# omca_to_mega_1.net
KiCad netlist of a schematic drawn in EAGLE
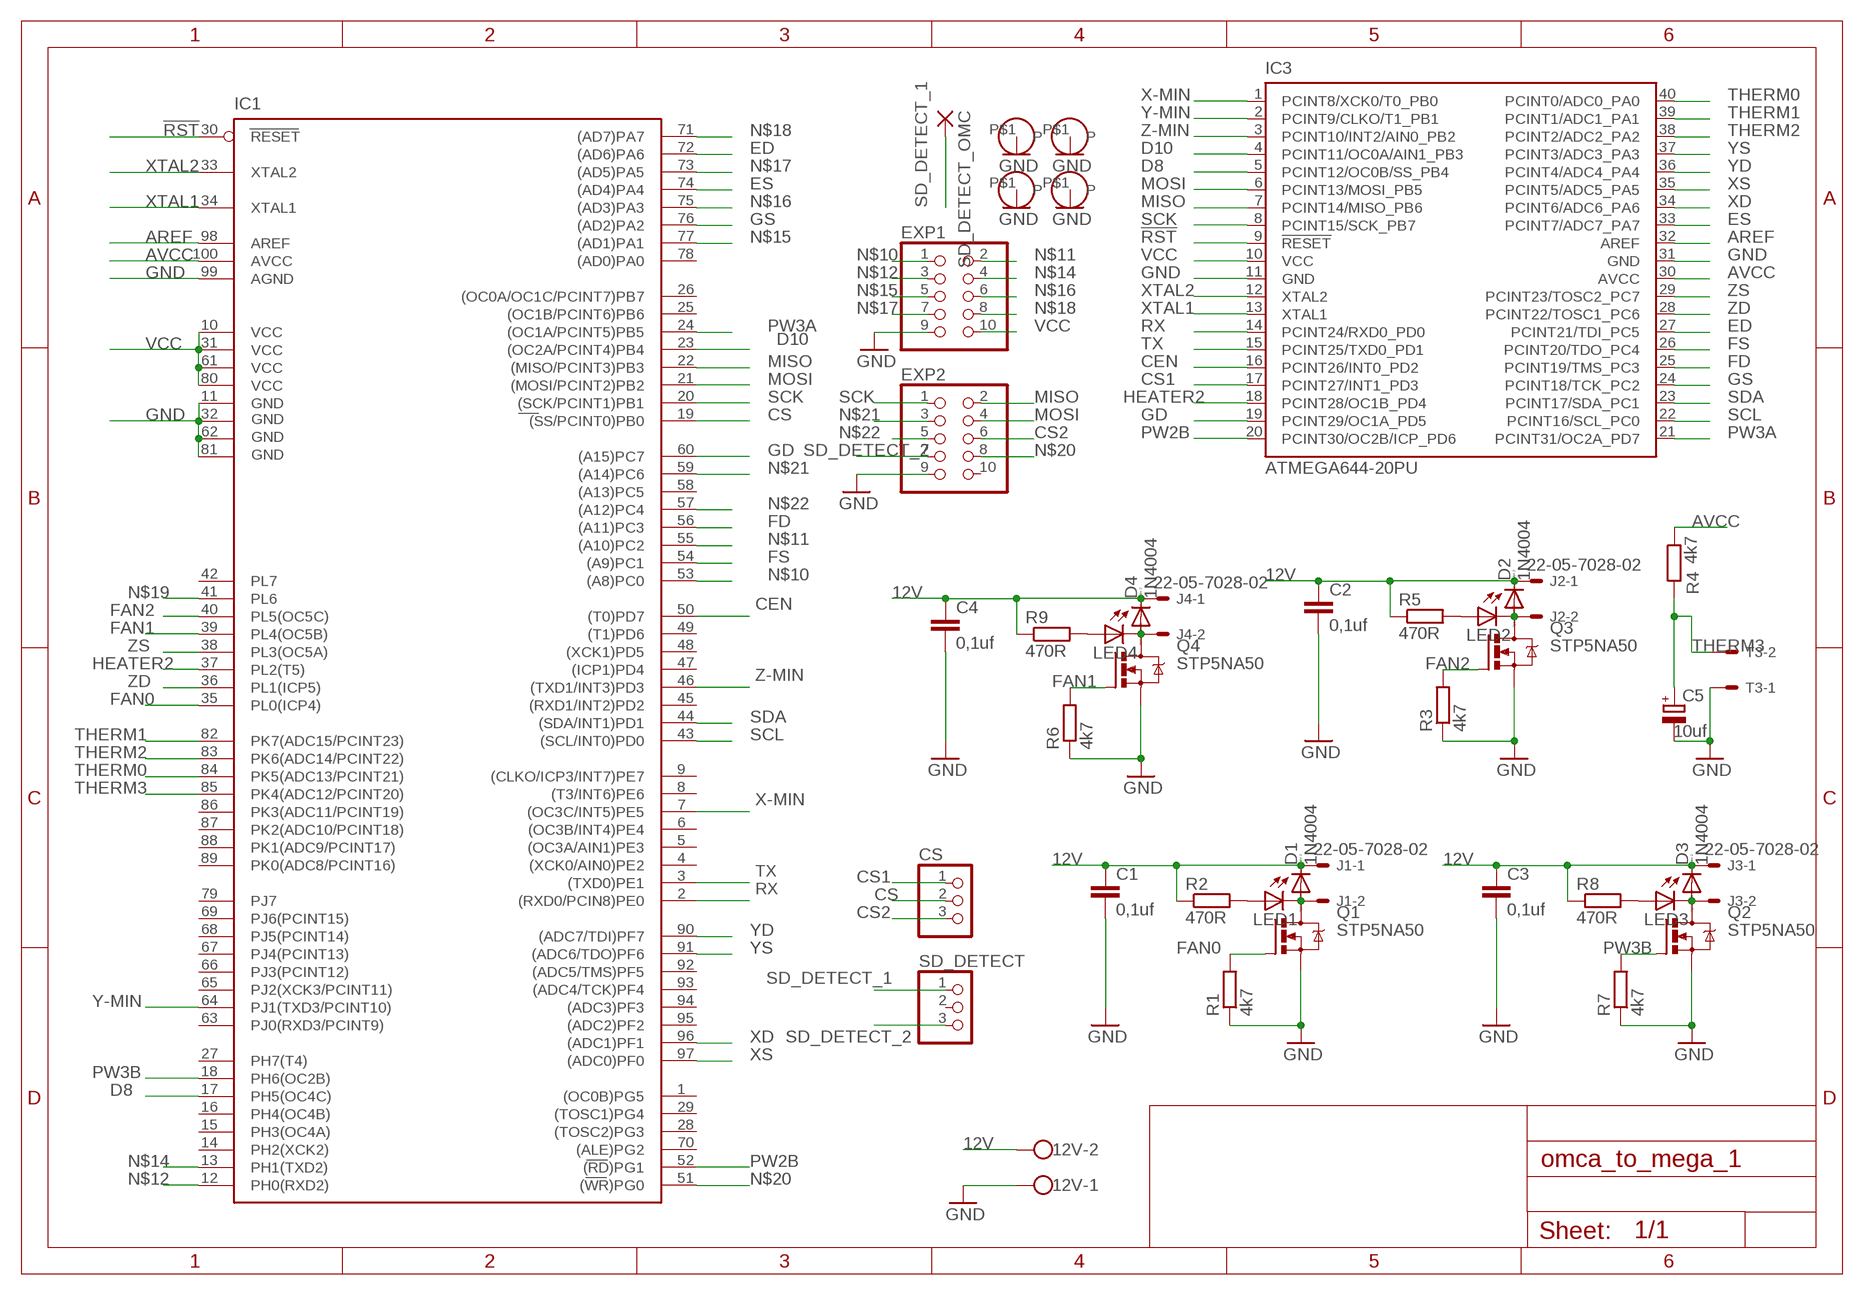
[diagram p0: schematic, sheet 1]

(export (version "E")
  (design (tool "Eeschema 10.0.6"))
  (components
    (comp (ref "12V")
      (value "W237-102")
      (footprint "eagle-import:W237-102")
      (fields (field (name "MPN") "237-102"))
      (libsource (lib "eagle-import") (part "W237-102"))
    )
    (comp (ref "C1")
      (value "0,1uf")
      (footprint "eagle-import:C025-024X044")
      (fields (field (name "MF") "VISHAY") (field (name "MPN") "K104K15X7RF53L2"))
      (libsource (lib "eagle-import") (part "C-EU025-024X044"))
    )
    (comp (ref "C2")
      (value "0,1uf")
      (footprint "eagle-import:C025-024X044")
      (fields (field (name "MF") "VISHAY") (field (name "MPN") "K104K15X7RF53L2"))
      (libsource (lib "eagle-import") (part "C-EU025-024X044"))
    )
    (comp (ref "C3")
      (value "0,1uf")
      (footprint "eagle-import:C025-024X044")
      (fields (field (name "MF") "VISHAY") (field (name "MPN") "K104K15X7RF53L2"))
      (libsource (lib "eagle-import") (part "C-EU025-024X044"))
    )
    (comp (ref "C4")
      (value "0,1uf")
      (footprint "eagle-import:C025-024X044")
      (fields (field (name "MF") "VISHAY") (field (name "MPN") "K104K15X7RF53L2"))
      (libsource (lib "eagle-import") (part "C-EU025-024X044"))
    )
    (comp (ref "C5")
      (value "10uf")
      (footprint "eagle-import:TT2D4")
      (fields (field (name "MF") "RUBYCON") (field (name "MPN") "100YXF10MEFC6.3X11"))
      (libsource (lib "eagle-import") (part "CPOL-EUTT2D4"))
    )
    (comp (ref "CS")
      (value "PINHD-1X3")
      (footprint "eagle-import:1X03")
      (libsource (lib "eagle-import") (part "PINHD-1X3"))
    )
    (comp (ref "D1")
      (value "1N4004")
      (footprint "eagle-import:D-7.5")
      (fields (field (name "MF") "ON SEMICONDUCTOR") (field (name "MPN") "1N4004RL"))
      (libsource (lib "eagle-import") (part "DIODE-D-7.5"))
    )
    (comp (ref "D2")
      (value "1N4004")
      (footprint "eagle-import:D-7.5")
      (fields (field (name "MF") "ON SEMICONDUCTOR") (field (name "MPN") "1N4004RL"))
      (libsource (lib "eagle-import") (part "DIODE-D-7.5"))
    )
    (comp (ref "D3")
      (value "1N4004")
      (footprint "eagle-import:D-7.5")
      (fields (field (name "MF") "ON SEMICONDUCTOR") (field (name "MPN") "1N4004RL"))
      (libsource (lib "eagle-import") (part "DIODE-D-7.5"))
    )
    (comp (ref "D4")
      (value "1N4004")
      (footprint "eagle-import:D-7.5")
      (fields (field (name "MF") "ON SEMICONDUCTOR") (field (name "MPN") "1N4004RL"))
      (libsource (lib "eagle-import") (part "DIODE-D-7.5"))
    )
    (comp (ref "EXP1")
      (value "PINHD-2X5")
      (footprint "eagle-import:2X05")
      (libsource (lib "eagle-import") (part "PINHD-2X5"))
    )
    (comp (ref "EXP2")
      (value "PINHD-2X5")
      (footprint "eagle-import:2X05")
      (libsource (lib "eagle-import") (part "PINHD-2X5"))
    )
    (comp (ref "IC1")
      (value "ATMEGA2560-16AU")
      (footprint "eagle-import:TQFP100")
      (libsource (lib "eagle-import") (part "ATMEGA2560AU2560-16"))
    )
    (comp (ref "IC3")
      (value "ATMEGA644-20PU")
      (footprint "eagle-import:DIL40")
      (fields
        (field (name "MF") "ATMEL")
        (field (name "MPN") "ATMEGA644-20PU")
        (field (name "OC_FARNELL") "1288340")
      )
      (libsource (lib "eagle-import") (part "ATMEGA644-PU20"))
    )
    (comp (ref "J1")
      (value "22-05-7028-02")
      (footprint "eagle-import:7395-02")
      (fields
        (field (name "MF") "MOLEX")
        (field (name "MPN") "22-05-7028")
        (field (name "OC_FARNELL") "9731601")
      )
      (libsource (lib "eagle-import") (part "22-?-0205-7028"))
    )
    (comp (ref "J2")
      (value "22-05-7028-02")
      (footprint "eagle-import:7395-02")
      (fields
        (field (name "MF") "MOLEX")
        (field (name "MPN") "22-05-7028")
        (field (name "OC_FARNELL") "9731601")
      )
      (libsource (lib "eagle-import") (part "22-?-0205-7028"))
    )
    (comp (ref "J3")
      (value "22-05-7028-02")
      (footprint "eagle-import:7395-02")
      (fields
        (field (name "MF") "MOLEX")
        (field (name "MPN") "22-05-7028")
        (field (name "OC_FARNELL") "9731601")
      )
      (libsource (lib "eagle-import") (part "22-?-0205-7028"))
    )
    (comp (ref "J4")
      (value "22-05-7028-02")
      (footprint "eagle-import:7395-02")
      (fields
        (field (name "MF") "MOLEX")
        (field (name "MPN") "22-05-7028")
        (field (name "OC_FARNELL") "9731601")
      )
      (libsource (lib "eagle-import") (part "22-?-0205-7028"))
    )
    (comp (ref "LED1")
      (value "LED3MM")
      (footprint "eagle-import:LED3MM")
      (fields (field (name "MF") "KINGBRIGHT") (field (name "MPN") "L-93WEYW"))
      (libsource (lib "eagle-import") (part "LED3MM"))
    )
    (comp (ref "LED2")
      (value "LED3MM")
      (footprint "eagle-import:LED3MM")
      (fields (field (name "MF") "KINGBRIGHT") (field (name "MPN") "L-93WEYW"))
      (libsource (lib "eagle-import") (part "LED3MM"))
    )
    (comp (ref "LED3")
      (value "LED3MM")
      (footprint "eagle-import:LED3MM")
      (fields (field (name "MF") "KINGBRIGHT") (field (name "MPN") "L-93WEYW"))
      (libsource (lib "eagle-import") (part "LED3MM"))
    )
    (comp (ref "LED4")
      (value "LED3MM")
      (footprint "eagle-import:LED3MM")
      (fields (field (name "MF") "KINGBRIGHT") (field (name "MPN") "L-93WEYW"))
      (libsource (lib "eagle-import") (part "LED3MM"))
    )
    (comp (ref "Q1")
      (value "STP5NA50")
      (footprint "eagle-import:TO220BV")
      (fields (field (name "MF") "STMICROELECTRONICS") (field (name "MPN") "STP55NF06L."))
      (libsource (lib "eagle-import") (part "STP5NA50"))
    )
    (comp (ref "Q2")
      (value "STP5NA50")
      (footprint "eagle-import:TO220BV")
      (fields (field (name "MF") "STMICROELECTRONICS") (field (name "MPN") "STP55NF06L."))
      (libsource (lib "eagle-import") (part "STP5NA50"))
    )
    (comp (ref "Q3")
      (value "STP5NA50")
      (footprint "eagle-import:TO220BV")
      (fields (field (name "MF") "STMICROELECTRONICS") (field (name "MPN") "STP55NF06L."))
      (libsource (lib "eagle-import") (part "STP5NA50"))
    )
    (comp (ref "Q4")
      (value "STP5NA50")
      (footprint "eagle-import:TO220BV")
      (fields (field (name "MF") "STMICROELECTRONICS") (field (name "MPN") "STP55NF06L."))
      (libsource (lib "eagle-import") (part "STP5NA50"))
    )
    (comp (ref "R1")
      (value "4k7")
      (footprint "eagle-import:0204_7")
      (fields (field (name "MF") "WELWYN") (field (name "MPN") "MFR4 10K 1%"))
      (libsource (lib "eagle-import") (part "resistor_R-EU_0204/7"))
    )
    (comp (ref "R2")
      (value "470R")
      (footprint "eagle-import:0204_7")
      (fields (field (name "MF") "WELWYN") (field (name "MPN") "MFR4 470R 1%"))
      (libsource (lib "eagle-import") (part "resistor_R-EU_0204/7"))
    )
    (comp (ref "R3")
      (value "4k7")
      (footprint "eagle-import:0204_7")
      (fields (field (name "MF") "WELWYN") (field (name "MPN") "MFR4 10K 1%"))
      (libsource (lib "eagle-import") (part "resistor_R-EU_0204/7"))
    )
    (comp (ref "R4")
      (value "4k7")
      (footprint "eagle-import:0204_7")
      (fields (field (name "MF") "WELWYN") (field (name "MPN") "MFR4 4K7 1%"))
      (libsource (lib "eagle-import") (part "R-EU_0204/7"))
    )
    (comp (ref "R5")
      (value "470R")
      (footprint "eagle-import:0204_7")
      (fields (field (name "MF") "WELWYN") (field (name "MPN") "MFR4 470R 1%"))
      (libsource (lib "eagle-import") (part "resistor_R-EU_0204/7"))
    )
    (comp (ref "R6")
      (value "4k7")
      (footprint "eagle-import:0204_7")
      (fields (field (name "MF") "WELWYN") (field (name "MPN") "MFR4 10K 1%"))
      (libsource (lib "eagle-import") (part "resistor_R-EU_0204/7"))
    )
    (comp (ref "R7")
      (value "4k7")
      (footprint "eagle-import:0204_7")
      (fields (field (name "MF") "WELWYN") (field (name "MPN") "MFR4 10K 1%"))
      (libsource (lib "eagle-import") (part "resistor_R-EU_0204/7"))
    )
    (comp (ref "R8")
      (value "470R")
      (footprint "eagle-import:0204_7")
      (fields (field (name "MF") "WELWYN") (field (name "MPN") "MFR4 470R 1%"))
      (libsource (lib "eagle-import") (part "resistor_R-EU_0204/7"))
    )
    (comp (ref "R9")
      (value "470R")
      (footprint "eagle-import:0204_7")
      (fields (field (name "MF") "WELWYN") (field (name "MPN") "MFR4 470R 1%"))
      (libsource (lib "eagle-import") (part "resistor_R-EU_0204/7"))
    )
    (comp (ref "SD_DETECT")
      (value "PINHD-1X3")
      (footprint "eagle-import:1X03")
      (libsource (lib "eagle-import") (part "PINHD-1X3"))
    )
    (comp (ref "SD_DETECT_OMC")
      (value "1,6/0,8")
      (footprint "eagle-import:1,6_0,8")
      (libsource (lib "eagle-import") (part "1,6/0,8"))
    )
    (comp (ref "T3")
      (value "22-05-7028-02")
      (footprint "eagle-import:7395-02")
      (fields
        (field (name "MF") "MOLEX")
        (field (name "MPN") "22-05-7028")
        (field (name "OC_FARNELL") "9731601")
      )
      (libsource (lib "eagle-import") (part "22-?-0205-7028"))
    )
    (comp (ref "U$2")
      (value "HOLE")
      (footprint "eagle-import:HOLE")
      (libsource (lib "eagle-import") (part "HOLE"))
    )
    (comp (ref "U$3")
      (value "HOLE")
      (footprint "eagle-import:HOLE")
      (libsource (lib "eagle-import") (part "HOLE"))
    )
    (comp (ref "U$4")
      (value "HOLE")
      (footprint "eagle-import:HOLE")
      (libsource (lib "eagle-import") (part "HOLE"))
    )
    (comp (ref "U$5")
      (value "HOLE")
      (footprint "eagle-import:HOLE")
      (libsource (lib "eagle-import") (part "HOLE"))
    )
  )
  (nets
    (net (code "1") (name "/12V") (class "Default")
      (node (ref "12V") (pin "2") (pinfunction "KL_2") (pintype "passive"))
      (node (ref "C1") (pin "1") (pinfunction "1_1") (pintype "passive"))
      (node (ref "C2") (pin "1") (pinfunction "1_1") (pintype "passive"))
      (node (ref "C3") (pin "1") (pinfunction "1_1") (pintype "passive"))
      (node (ref "C4") (pin "1") (pinfunction "1_1") (pintype "passive"))
      (node (ref "D1") (pin "C") (pinfunction "C_C") (pintype "passive"))
      (node (ref "D2") (pin "C") (pinfunction "C_C") (pintype "passive"))
      (node (ref "D3") (pin "C") (pinfunction "C_C") (pintype "passive"))
      (node (ref "D4") (pin "C") (pinfunction "C_C") (pintype "passive"))
      (node (ref "J1") (pin "1") (pinfunction "S_1") (pintype "passive"))
      (node (ref "J2") (pin "1") (pinfunction "S_1") (pintype "passive"))
      (node (ref "J3") (pin "1") (pinfunction "S_1") (pintype "passive"))
      (node (ref "J4") (pin "1") (pinfunction "S_1") (pintype "passive"))
      (node (ref "R2") (pin "1") (pinfunction "1_1") (pintype "passive"))
      (node (ref "R5") (pin "1") (pinfunction "1_1") (pintype "passive"))
      (node (ref "R8") (pin "1") (pinfunction "1_1") (pintype "passive"))
      (node (ref "R9") (pin "1") (pinfunction "1_1") (pintype "passive"))
    )
    (net (code "2") (name "/AREF") (class "Default")
      (node (ref "IC1") (pin "98") (pinfunction "AREF_98") (pintype "bidirectional"))
      (node (ref "IC3") (pin "32") (pinfunction "AREF_32") (pintype "passive"))
    )
    (net (code "3") (name "/AVCC") (class "Default")
      (node (ref "IC1") (pin "100") (pinfunction "AVCC_100") (pintype "power_in"))
      (node (ref "IC3") (pin "30") (pinfunction "AVCC_30") (pintype "power_in"))
      (node (ref "R4") (pin "1") (pinfunction "1_1") (pintype "passive"))
    )
    (net (code "4") (name "/CEN") (class "Default")
      (node (ref "IC1") (pin "50") (pinfunction "(T0)PD7_50") (pintype "bidirectional"))
      (node (ref "IC3") (pin "16") (pinfunction "PCINT26/INT0_PD2_16") (pintype "bidirectional"))
    )
    (net (code "5") (name "/CS") (class "Default")
      (node (ref "CS") (pin "2") (pinfunction "2_2") (pintype "passive"))
      (node (ref "IC1") (pin "19") (pinfunction "(SS/PCINT0)PB0_19") (pintype "bidirectional"))
    )
    (net (code "6") (name "/CS1") (class "Default")
      (node (ref "CS") (pin "1") (pinfunction "1_1") (pintype "passive"))
      (node (ref "IC3") (pin "17") (pinfunction "PCINT27/INT1_PD3_17") (pintype "bidirectional"))
    )
    (net (code "7") (name "/CS2") (class "Default")
      (node (ref "CS") (pin "3") (pinfunction "3_3") (pintype "passive"))
      (node (ref "EXP2") (pin "6") (pinfunction "6_6") (pintype "passive"))
    )
    (net (code "8") (name "/D8") (class "Default")
      (node (ref "IC1") (pin "17") (pinfunction "PH5(OC4C)_17") (pintype "bidirectional"))
      (node (ref "IC3") (pin "5") (pinfunction "PCINT12/OC0B/SS_PB4_5") (pintype "bidirectional"))
    )
    (net (code "9") (name "/D10") (class "Default")
      (node (ref "IC1") (pin "23") (pinfunction "(OC2A/PCINT4)PB4_23") (pintype "bidirectional"))
      (node (ref "IC3") (pin "4") (pinfunction "PCINT11/OC0A/AIN1_PB3_4") (pintype "bidirectional"))
    )
    (net (code "10") (name "/ED") (class "Default")
      (node (ref "IC1") (pin "72") (pinfunction "(AD6)PA6_72") (pintype "bidirectional"))
      (node (ref "IC3") (pin "27") (pinfunction "PCINT21/TDI_PC5_27") (pintype "bidirectional"))
    )
    (net (code "11") (name "/ES") (class "Default")
      (node (ref "IC1") (pin "74") (pinfunction "(AD4)PA4_74") (pintype "bidirectional"))
      (node (ref "IC3") (pin "33") (pinfunction "PCINT7/ADC7_PA7_33") (pintype "bidirectional"))
    )
    (net (code "12") (name "/FAN0") (class "Default")
      (node (ref "IC1") (pin "35") (pinfunction "PL0(ICP4)_35") (pintype "bidirectional"))
      (node (ref "Q1") (pin "G") (pinfunction "G_G") (pintype "passive"))
      (node (ref "R1") (pin "2") (pinfunction "2_2") (pintype "passive"))
    )
    (net (code "13") (name "/FAN1") (class "Default")
      (node (ref "IC1") (pin "39") (pinfunction "PL4(OC5B)_39") (pintype "bidirectional"))
      (node (ref "Q4") (pin "G") (pinfunction "G_G") (pintype "passive"))
      (node (ref "R6") (pin "2") (pinfunction "2_2") (pintype "passive"))
    )
    (net (code "14") (name "/FAN2") (class "Default")
      (node (ref "IC1") (pin "40") (pinfunction "PL5(OC5C)_40") (pintype "bidirectional"))
      (node (ref "Q3") (pin "G") (pinfunction "G_G") (pintype "passive"))
      (node (ref "R3") (pin "2") (pinfunction "2_2") (pintype "passive"))
    )
    (net (code "15") (name "/FD") (class "Default")
      (node (ref "IC1") (pin "56") (pinfunction "(A11)PC3_56") (pintype "bidirectional"))
      (node (ref "IC3") (pin "25") (pinfunction "PCINT19/TMS_PC3_25") (pintype "bidirectional"))
    )
    (net (code "16") (name "/FS") (class "Default")
      (node (ref "IC1") (pin "54") (pinfunction "(A9)PC1_54") (pintype "bidirectional"))
      (node (ref "IC3") (pin "26") (pinfunction "PCINT20/TDO_PC4_26") (pintype "bidirectional"))
    )
    (net (code "17") (name "/GD") (class "Default")
      (node (ref "IC1") (pin "60") (pinfunction "(A15)PC7_60") (pintype "bidirectional"))
      (node (ref "IC3") (pin "19") (pinfunction "PCINT29/OC1A_PD5_19") (pintype "bidirectional"))
    )
    (net (code "18") (name "/GS") (class "Default")
      (node (ref "IC1") (pin "76") (pinfunction "(AD2)PA2_76") (pintype "bidirectional"))
      (node (ref "IC3") (pin "24") (pinfunction "PCINT18/TCK_PC2_24") (pintype "bidirectional"))
    )
    (net (code "19") (name "/HEATER2") (class "Default")
      (node (ref "IC1") (pin "37") (pinfunction "PL2(T5)_37") (pintype "bidirectional"))
      (node (ref "IC3") (pin "18") (pinfunction "PCINT28/OC1B_PD4_18") (pintype "bidirectional"))
    )
    (net (code "20") (name "/MISO") (class "Default")
      (node (ref "EXP2") (pin "2") (pinfunction "2_2") (pintype "passive"))
      (node (ref "IC1") (pin "22") (pinfunction "(MISO/PCINT3)PB3_22") (pintype "bidirectional"))
      (node (ref "IC3") (pin "7") (pinfunction "PCINT14/MISO_PB6_7") (pintype "bidirectional"))
    )
    (net (code "21") (name "/MOSI") (class "Default")
      (node (ref "EXP2") (pin "4") (pinfunction "4_4") (pintype "passive"))
      (node (ref "IC1") (pin "21") (pinfunction "(MOSI/PCINT2)PB2_21") (pintype "bidirectional"))
      (node (ref "IC3") (pin "6") (pinfunction "PCINT13/MOSI_PB5_6") (pintype "bidirectional"))
    )
    (net (code "22") (name "/N$10") (class "Default")
      (node (ref "EXP1") (pin "1") (pinfunction "1_1") (pintype "passive"))
      (node (ref "IC1") (pin "53") (pinfunction "(A8)PC0_53") (pintype "bidirectional"))
    )
    (net (code "23") (name "/N$11") (class "Default")
      (node (ref "EXP1") (pin "2") (pinfunction "2_2") (pintype "passive"))
      (node (ref "IC1") (pin "55") (pinfunction "(A10)PC2_55") (pintype "bidirectional"))
    )
    (net (code "24") (name "/N$12") (class "Default")
      (node (ref "EXP1") (pin "3") (pinfunction "3_3") (pintype "passive"))
      (node (ref "IC1") (pin "12") (pinfunction "PH0(RXD2)_12") (pintype "bidirectional"))
    )
    (net (code "25") (name "/N$14") (class "Default")
      (node (ref "EXP1") (pin "4") (pinfunction "4_4") (pintype "passive"))
      (node (ref "IC1") (pin "13") (pinfunction "PH1(TXD2)_13") (pintype "bidirectional"))
    )
    (net (code "26") (name "/N$15") (class "Default")
      (node (ref "EXP1") (pin "5") (pinfunction "5_5") (pintype "passive"))
      (node (ref "IC1") (pin "77") (pinfunction "(AD1)PA1_77") (pintype "bidirectional"))
    )
    (net (code "27") (name "/N$16") (class "Default")
      (node (ref "EXP1") (pin "6") (pinfunction "6_6") (pintype "passive"))
      (node (ref "IC1") (pin "75") (pinfunction "(AD3)PA3_75") (pintype "bidirectional"))
    )
    (net (code "28") (name "/N$17") (class "Default")
      (node (ref "EXP1") (pin "7") (pinfunction "7_7") (pintype "passive"))
      (node (ref "IC1") (pin "73") (pinfunction "(AD5)PA5_73") (pintype "bidirectional"))
    )
    (net (code "29") (name "/N$18") (class "Default")
      (node (ref "EXP1") (pin "8") (pinfunction "8_8") (pintype "passive"))
      (node (ref "IC1") (pin "71") (pinfunction "(AD7)PA7_71") (pintype "bidirectional"))
    )
    (net (code "30") (name "/N$19") (class "Default")
      (node (ref "IC1") (pin "41") (pinfunction "PL6_41") (pintype "bidirectional"))
    )
    (net (code "31") (name "/N$20") (class "Default")
      (node (ref "EXP2") (pin "8") (pinfunction "8_8") (pintype "passive"))
      (node (ref "IC1") (pin "51") (pinfunction "(WR)PG0_51") (pintype "bidirectional"))
    )
    (net (code "32") (name "/N$21") (class "Default")
      (node (ref "EXP2") (pin "3") (pinfunction "3_3") (pintype "passive"))
      (node (ref "IC1") (pin "59") (pinfunction "(A14)PC6_59") (pintype "bidirectional"))
    )
    (net (code "33") (name "/N$22") (class "Default")
      (node (ref "EXP2") (pin "5") (pinfunction "5_5") (pintype "passive"))
      (node (ref "IC1") (pin "57") (pinfunction "(A12)PC4_57") (pintype "bidirectional"))
    )
    (net (code "34") (name "/PW2B") (class "Default")
      (node (ref "IC1") (pin "52") (pinfunction "(RD)PG1_52") (pintype "bidirectional"))
      (node (ref "IC3") (pin "20") (pinfunction "PCINT30/OC2B/ICP_PD6_20") (pintype "bidirectional"))
    )
    (net (code "35") (name "/PW3A") (class "Default")
      (node (ref "IC1") (pin "24") (pinfunction "(OC1A/PCINT5)PB5_24") (pintype "bidirectional"))
      (node (ref "IC3") (pin "21") (pinfunction "PCINT31/OC2A_PD7_21") (pintype "bidirectional"))
    )
    (net (code "36") (name "/PW3B") (class "Default")
      (node (ref "IC1") (pin "18") (pinfunction "PH6(OC2B)_18") (pintype "bidirectional"))
      (node (ref "Q2") (pin "G") (pinfunction "G_G") (pintype "passive"))
      (node (ref "R7") (pin "2") (pinfunction "2_2") (pintype "passive"))
    )
    (net (code "37") (name "/RX") (class "Default")
      (node (ref "IC1") (pin "2") (pinfunction "(RXD0/PCIN8)PE0_2") (pintype "bidirectional"))
      (node (ref "IC3") (pin "14") (pinfunction "PCINT24/RXD0_PD0_14") (pintype "bidirectional"))
    )
    (net (code "38") (name "/SCK") (class "Default")
      (node (ref "EXP2") (pin "1") (pinfunction "1_1") (pintype "passive"))
      (node (ref "IC1") (pin "20") (pinfunction "(SCK/PCINT1)PB1_20") (pintype "bidirectional"))
      (node (ref "IC3") (pin "8") (pinfunction "PCINT15/SCK_PB7_8") (pintype "bidirectional"))
    )
    (net (code "39") (name "/SCL") (class "Default")
      (node (ref "IC1") (pin "43") (pinfunction "(SCL/INT0)PD0_43") (pintype "bidirectional"))
      (node (ref "IC3") (pin "22") (pinfunction "PCINT16/SCL_PC0_22") (pintype "bidirectional"))
    )
    (net (code "40") (name "/SDA") (class "Default")
      (node (ref "IC1") (pin "44") (pinfunction "(SDA/INT1)PD1_44") (pintype "bidirectional"))
      (node (ref "IC3") (pin "23") (pinfunction "PCINT17/SDA_PC1_23") (pintype "bidirectional"))
    )
    (net (code "41") (name "/SD_DETECT_1") (class "Default")
      (node (ref "SD_DETECT") (pin "1") (pinfunction "1_1") (pintype "passive"))
      (node (ref "SD_DETECT_OMC") (pin "1") (pinfunction "P_1") (pintype "passive"))
    )
    (net (code "42") (name "/SD_DETECT_2") (class "Default")
      (node (ref "EXP2") (pin "7") (pinfunction "7_7") (pintype "passive"))
      (node (ref "SD_DETECT") (pin "3") (pinfunction "3_3") (pintype "passive"))
    )
    (net (code "43") (name "/THERM0") (class "Default")
      (node (ref "IC1") (pin "84") (pinfunction "PK5(ADC13/PCINT21)_84") (pintype "bidirectional"))
      (node (ref "IC3") (pin "40") (pinfunction "PCINT0/ADC0_PA0_40") (pintype "bidirectional"))
    )
    (net (code "44") (name "/THERM1") (class "Default")
      (node (ref "IC1") (pin "82") (pinfunction "PK7(ADC15/PCINT23)_82") (pintype "bidirectional"))
      (node (ref "IC3") (pin "39") (pinfunction "PCINT1/ADC1_PA1_39") (pintype "bidirectional"))
    )
    (net (code "45") (name "/THERM2") (class "Default")
      (node (ref "IC1") (pin "83") (pinfunction "PK6(ADC14/PCINT22)_83") (pintype "bidirectional"))
      (node (ref "IC3") (pin "38") (pinfunction "PCINT2/ADC2_PA2_38") (pintype "bidirectional"))
    )
    (net (code "46") (name "/THERM3") (class "Default")
      (node (ref "C5") (pin "+") (pinfunction "+_+") (pintype "passive"))
      (node (ref "IC1") (pin "85") (pinfunction "PK4(ADC12/PCINT20)_85") (pintype "bidirectional"))
      (node (ref "R4") (pin "2") (pinfunction "2_2") (pintype "passive"))
      (node (ref "T3") (pin "2") (pinfunction "S_2") (pintype "passive"))
    )
    (net (code "47") (name "/TX") (class "Default")
      (node (ref "IC1") (pin "3") (pinfunction "(TXD0)PE1_3") (pintype "bidirectional"))
      (node (ref "IC3") (pin "15") (pinfunction "PCINT25/TXD0_PD1_15") (pintype "bidirectional"))
    )
    (net (code "48") (name "/VCC") (class "Default")
      (node (ref "EXP1") (pin "10") (pinfunction "10_10") (pintype "passive"))
      (node (ref "IC1") (pin "10") (pinfunction "VCC_10") (pintype "power_in"))
      (node (ref "IC1") (pin "31") (pinfunction "VCC1_31") (pintype "power_in"))
      (node (ref "IC1") (pin "61") (pinfunction "VCC2_61") (pintype "power_in"))
      (node (ref "IC1") (pin "80") (pinfunction "VCC3_80") (pintype "power_in"))
      (node (ref "IC3") (pin "10") (pinfunction "VCC_10") (pintype "power_in"))
    )
    (net (code "49") (name "/X-MIN") (class "Default")
      (node (ref "IC1") (pin "7") (pinfunction "(OC3C/INT5)PE5_7") (pintype "bidirectional"))
      (node (ref "IC3") (pin "1") (pinfunction "PCINT8/XCK0/T0_PB0_1") (pintype "bidirectional"))
    )
    (net (code "50") (name "/XD") (class "Default")
      (node (ref "IC1") (pin "96") (pinfunction "(ADC1)PF1_96") (pintype "bidirectional"))
      (node (ref "IC3") (pin "34") (pinfunction "PCINT6/ADC6_PA6_34") (pintype "bidirectional"))
    )
    (net (code "51") (name "/XS") (class "Default")
      (node (ref "IC1") (pin "97") (pinfunction "(ADC0)PF0_97") (pintype "bidirectional"))
      (node (ref "IC3") (pin "35") (pinfunction "PCINT5/ADC5_PA5_35") (pintype "bidirectional"))
    )
    (net (code "52") (name "/XTAL1") (class "Default")
      (node (ref "IC1") (pin "34") (pinfunction "XTAL1_34") (pintype "input"))
      (node (ref "IC3") (pin "13") (pinfunction "XTAL1_13") (pintype "input"))
    )
    (net (code "53") (name "/XTAL2") (class "Default")
      (node (ref "IC1") (pin "33") (pinfunction "XTAL2_33") (pintype "output"))
      (node (ref "IC3") (pin "12") (pinfunction "XTAL2_12") (pintype "output"))
    )
    (net (code "54") (name "/Y-MIN") (class "Default")
      (node (ref "IC1") (pin "64") (pinfunction "PJ1(TXD3/PCINT10)_64") (pintype "bidirectional"))
      (node (ref "IC3") (pin "2") (pinfunction "PCINT9/CLKO/T1_PB1_2") (pintype "bidirectional"))
    )
    (net (code "55") (name "/YD") (class "Default")
      (node (ref "IC1") (pin "90") (pinfunction "(ADC7/TDI)PF7_90") (pintype "bidirectional"))
      (node (ref "IC3") (pin "36") (pinfunction "PCINT4/ADC4_PA4_36") (pintype "bidirectional"))
    )
    (net (code "56") (name "/YS") (class "Default")
      (node (ref "IC1") (pin "91") (pinfunction "(ADC6/TDO)PF6_91") (pintype "bidirectional"))
      (node (ref "IC3") (pin "37") (pinfunction "PCINT3/ADC3_PA3_37") (pintype "bidirectional"))
    )
    (net (code "57") (name "/Z-MIN") (class "Default")
      (node (ref "IC1") (pin "46") (pinfunction "(TXD1/INT3)PD3_46") (pintype "bidirectional"))
      (node (ref "IC3") (pin "3") (pinfunction "PCINT10/INT2/AIN0_PB2_3") (pintype "bidirectional"))
    )
    (net (code "58") (name "/ZD") (class "Default")
      (node (ref "IC1") (pin "36") (pinfunction "PL1(ICP5)_36") (pintype "bidirectional"))
      (node (ref "IC3") (pin "28") (pinfunction "PCINT22/TOSC1_PC6_28") (pintype "bidirectional"))
    )
    (net (code "59") (name "/ZS") (class "Default")
      (node (ref "IC1") (pin "38") (pinfunction "PL3(OC5A)_38") (pintype "bidirectional"))
      (node (ref "IC3") (pin "29") (pinfunction "PCINT23/TOSC2_PC7_29") (pintype "bidirectional"))
    )
    (net (code "60") (name "/~{RST}") (class "Default")
      (node (ref "IC1") (pin "30") (pinfunction "RESET_30") (pintype "input"))
      (node (ref "IC3") (pin "9") (pinfunction "~{RESET}_9") (pintype "input"))
    )
    (net (code "61") (name "GND") (class "Default")
      (node (ref "12V") (pin "1") (pinfunction "KL_1") (pintype "passive"))
      (node (ref "C1") (pin "2") (pinfunction "2_2") (pintype "passive"))
      (node (ref "C2") (pin "2") (pinfunction "2_2") (pintype "passive"))
      (node (ref "C3") (pin "2") (pinfunction "2_2") (pintype "passive"))
      (node (ref "C4") (pin "2") (pinfunction "2_2") (pintype "passive"))
      (node (ref "C5") (pin "-") (pinfunction "-_-") (pintype "passive"))
      (node (ref "EXP1") (pin "9") (pinfunction "9_9") (pintype "passive"))
      (node (ref "EXP2") (pin "9") (pinfunction "9_9") (pintype "passive"))
      (node (ref "IC1") (pin "11") (pinfunction "GND_11") (pintype "power_in"))
      (node (ref "IC1") (pin "32") (pinfunction "GND1_32") (pintype "power_in"))
      (node (ref "IC1") (pin "62") (pinfunction "GND2_62") (pintype "power_in"))
      (node (ref "IC1") (pin "81") (pinfunction "GND3_81") (pintype "power_in"))
      (node (ref "IC1") (pin "99") (pinfunction "AGND_99") (pintype "power_in"))
      (node (ref "IC3") (pin "11") (pinfunction "GND_11") (pintype "power_in"))
      (node (ref "IC3") (pin "31") (pinfunction "GND_31") (pintype "power_in"))
      (node (ref "Q1") (pin "S") (pinfunction "S_S") (pintype "passive"))
      (node (ref "Q2") (pin "S") (pinfunction "S_S") (pintype "passive"))
      (node (ref "Q3") (pin "S") (pinfunction "S_S") (pintype "passive"))
      (node (ref "Q4") (pin "S") (pinfunction "S_S") (pintype "passive"))
      (node (ref "R1") (pin "1") (pinfunction "1_1") (pintype "passive"))
      (node (ref "R3") (pin "1") (pinfunction "1_1") (pintype "passive"))
      (node (ref "R6") (pin "1") (pinfunction "1_1") (pintype "passive"))
      (node (ref "R7") (pin "1") (pinfunction "1_1") (pintype "passive"))
      (node (ref "T3") (pin "1") (pinfunction "S_1") (pintype "passive"))
      (node (ref "U$2") (pin "P$1") (pinfunction "P_P$1") (pintype "bidirectional"))
      (node (ref "U$3") (pin "P$1") (pinfunction "P_P$1") (pintype "bidirectional"))
      (node (ref "U$4") (pin "P$1") (pinfunction "P_P$1") (pintype "bidirectional"))
      (node (ref "U$5") (pin "P$1") (pinfunction "P_P$1") (pintype "bidirectional"))
    )
    (net (code "62") (name "Net-(J1B-S)") (class "Default")
      (node (ref "D1") (pin "A") (pinfunction "A_A") (pintype "passive"))
      (node (ref "J1") (pin "2") (pinfunction "S_2") (pintype "passive"))
      (node (ref "LED1") (pin "K") (pinfunction "C_K") (pintype "passive"))
      (node (ref "Q1") (pin "D") (pinfunction "D_D") (pintype "passive"))
    )
    (net (code "63") (name "Net-(J2B-S)") (class "Default")
      (node (ref "D2") (pin "A") (pinfunction "A_A") (pintype "passive"))
      (node (ref "J2") (pin "2") (pinfunction "S_2") (pintype "passive"))
      (node (ref "LED2") (pin "K") (pinfunction "C_K") (pintype "passive"))
      (node (ref "Q3") (pin "D") (pinfunction "D_D") (pintype "passive"))
    )
    (net (code "64") (name "Net-(J3B-S)") (class "Default")
      (node (ref "D3") (pin "A") (pinfunction "A_A") (pintype "passive"))
      (node (ref "J3") (pin "2") (pinfunction "S_2") (pintype "passive"))
      (node (ref "LED3") (pin "K") (pinfunction "C_K") (pintype "passive"))
      (node (ref "Q2") (pin "D") (pinfunction "D_D") (pintype "passive"))
    )
    (net (code "65") (name "Net-(J4B-S)") (class "Default")
      (node (ref "D4") (pin "A") (pinfunction "A_A") (pintype "passive"))
      (node (ref "J4") (pin "2") (pinfunction "S_2") (pintype "passive"))
      (node (ref "LED4") (pin "K") (pinfunction "C_K") (pintype "passive"))
      (node (ref "Q4") (pin "D") (pinfunction "D_D") (pintype "passive"))
    )
    (net (code "66") (name "Net-(LED1-PadA)") (class "Default")
      (node (ref "LED1") (pin "A") (pinfunction "A_A") (pintype "passive"))
      (node (ref "R2") (pin "2") (pinfunction "2_2") (pintype "passive"))
    )
    (net (code "67") (name "Net-(LED2-PadA)") (class "Default")
      (node (ref "LED2") (pin "A") (pinfunction "A_A") (pintype "passive"))
      (node (ref "R5") (pin "2") (pinfunction "2_2") (pintype "passive"))
    )
    (net (code "68") (name "Net-(LED3-PadA)") (class "Default")
      (node (ref "LED3") (pin "A") (pinfunction "A_A") (pintype "passive"))
      (node (ref "R8") (pin "2") (pinfunction "2_2") (pintype "passive"))
    )
    (net (code "69") (name "Net-(LED4-PadA)") (class "Default")
      (node (ref "LED4") (pin "A") (pinfunction "A_A") (pintype "passive"))
      (node (ref "R9") (pin "2") (pinfunction "2_2") (pintype "passive"))
    )
    (net (code "70") (name "unconnected-(EXP2-Pad10)") (class "Default")
      (node (ref "EXP2") (pin "10") (pinfunction "10_10") (pintype "passive"))
    )
    (net (code "71") (name "unconnected-(IC1-(A13)PC5-Pad58)") (class "Default")
      (node (ref "IC1") (pin "58") (pinfunction "(A13)PC5_58") (pintype "bidirectional"))
    )
    (net (code "72") (name "unconnected-(IC1-(AD0)PA0-Pad78)") (class "Default")
      (node (ref "IC1") (pin "78") (pinfunction "(AD0)PA0_78") (pintype "bidirectional"))
    )
    (net (code "73") (name "unconnected-(IC1-(ADC2)PF2-Pad95)") (class "Default")
      (node (ref "IC1") (pin "95") (pinfunction "(ADC2)PF2_95") (pintype "bidirectional"))
    )
    (net (code "74") (name "unconnected-(IC1-(ADC3)PF3-Pad94)") (class "Default")
      (node (ref "IC1") (pin "94") (pinfunction "(ADC3)PF3_94") (pintype "bidirectional"))
    )
    (net (code "75") (name "unconnected-(IC1-(ADC4{slash}TCK)PF4-Pad93)") (class "Default")
      (node (ref "IC1") (pin "93") (pinfunction "(ADC4/TCK)PF4_93") (pintype "bidirectional"))
    )
    (net (code "76") (name "unconnected-(IC1-(ADC5{slash}TMS)PF5-Pad92)") (class "Default")
      (node (ref "IC1") (pin "92") (pinfunction "(ADC5/TMS)PF5_92") (pintype "bidirectional"))
    )
    (net (code "77") (name "unconnected-(IC1-(ALE)PG2-Pad70)") (class "Default")
      (node (ref "IC1") (pin "70") (pinfunction "(ALE)PG2_70") (pintype "bidirectional"))
    )
    (net (code "78") (name "unconnected-(IC1-(CLKO{slash}ICP3{slash}INT7)PE7-Pad9)") (class "Default")
      (node (ref "IC1") (pin "9") (pinfunction "(CLKO/ICP3/INT7)PE7_9") (pintype "bidirectional"))
    )
    (net (code "79") (name "unconnected-(IC1-(ICP1)PD4-Pad47)") (class "Default")
      (node (ref "IC1") (pin "47") (pinfunction "(ICP1)PD4_47") (pintype "bidirectional"))
    )
    (net (code "80") (name "unconnected-(IC1-(OC0A{slash}OC1C{slash}PCINT7)PB7-Pad26)") (class "Default")
      (node (ref "IC1") (pin "26") (pinfunction "(OC0A/OC1C/PCINT7)PB7_26") (pintype "bidirectional"))
    )
    (net (code "81") (name "unconnected-(IC1-(OC0B)PG5-Pad1)") (class "Default")
      (node (ref "IC1") (pin "1") (pinfunction "(OC0B)PG5_1") (pintype "bidirectional"))
    )
    (net (code "82") (name "unconnected-(IC1-(OC1B{slash}PCINT6)PB6-Pad25)") (class "Default")
      (node (ref "IC1") (pin "25") (pinfunction "(OC1B/PCINT6)PB6_25") (pintype "bidirectional"))
    )
    (net (code "83") (name "unconnected-(IC1-(OC3A{slash}AIN1)PE3-Pad5)") (class "Default")
      (node (ref "IC1") (pin "5") (pinfunction "(OC3A/AIN1)PE3_5") (pintype "bidirectional"))
    )
    (net (code "84") (name "unconnected-(IC1-(OC3B{slash}INT4)PE4-Pad6)") (class "Default")
      (node (ref "IC1") (pin "6") (pinfunction "(OC3B/INT4)PE4_6") (pintype "bidirectional"))
    )
    (net (code "85") (name "unconnected-(IC1-(RXD1{slash}INT2)PD2-Pad45)") (class "Default")
      (node (ref "IC1") (pin "45") (pinfunction "(RXD1/INT2)PD2_45") (pintype "bidirectional"))
    )
    (net (code "86") (name "unconnected-(IC1-(T1)PD6-Pad49)") (class "Default")
      (node (ref "IC1") (pin "49") (pinfunction "(T1)PD6_49") (pintype "bidirectional"))
    )
    (net (code "87") (name "unconnected-(IC1-(T3{slash}INT6)PE6-Pad8)") (class "Default")
      (node (ref "IC1") (pin "8") (pinfunction "(T3/INT6)PE6_8") (pintype "bidirectional"))
    )
    (net (code "88") (name "unconnected-(IC1-(TOSC1)PG4-Pad29)") (class "Default")
      (node (ref "IC1") (pin "29") (pinfunction "(TOSC1)PG4_29") (pintype "bidirectional"))
    )
    (net (code "89") (name "unconnected-(IC1-(TOSC2)PG3-Pad28)") (class "Default")
      (node (ref "IC1") (pin "28") (pinfunction "(TOSC2)PG3_28") (pintype "bidirectional"))
    )
    (net (code "90") (name "unconnected-(IC1-(XCK0{slash}AIN0)PE2-Pad4)") (class "Default")
      (node (ref "IC1") (pin "4") (pinfunction "(XCK0/AIN0)PE2_4") (pintype "bidirectional"))
    )
    (net (code "91") (name "unconnected-(IC1-(XCK1)PD5-Pad48)") (class "Default")
      (node (ref "IC1") (pin "48") (pinfunction "(XCK1)PD5_48") (pintype "bidirectional"))
    )
    (net (code "92") (name "unconnected-(IC1-PH2(XCK2)-Pad14)") (class "Default")
      (node (ref "IC1") (pin "14") (pinfunction "PH2(XCK2)_14") (pintype "bidirectional"))
    )
    (net (code "93") (name "unconnected-(IC1-PH3(OC4A)-Pad15)") (class "Default")
      (node (ref "IC1") (pin "15") (pinfunction "PH3(OC4A)_15") (pintype "bidirectional"))
    )
    (net (code "94") (name "unconnected-(IC1-PH4(OC4B)-Pad16)") (class "Default")
      (node (ref "IC1") (pin "16") (pinfunction "PH4(OC4B)_16") (pintype "bidirectional"))
    )
    (net (code "95") (name "unconnected-(IC1-PH7(T4)-Pad27)") (class "Default")
      (node (ref "IC1") (pin "27") (pinfunction "PH7(T4)_27") (pintype "bidirectional"))
    )
    (net (code "96") (name "unconnected-(IC1-PJ0(RXD3{slash}PCINT9)-Pad63)") (class "Default")
      (node (ref "IC1") (pin "63") (pinfunction "PJ0(RXD3/PCINT9)_63") (pintype "bidirectional"))
    )
    (net (code "97") (name "unconnected-(IC1-PJ2(XCK3{slash}PCINT11)-Pad65)") (class "Default")
      (node (ref "IC1") (pin "65") (pinfunction "PJ2(XCK3/PCINT11)_65") (pintype "bidirectional"))
    )
    (net (code "98") (name "unconnected-(IC1-PJ3(PCINT12)-Pad66)") (class "Default")
      (node (ref "IC1") (pin "66") (pinfunction "PJ3(PCINT12)_66") (pintype "bidirectional"))
    )
    (net (code "99") (name "unconnected-(IC1-PJ4(PCINT13)-Pad67)") (class "Default")
      (node (ref "IC1") (pin "67") (pinfunction "PJ4(PCINT13)_67") (pintype "bidirectional"))
    )
    (net (code "100") (name "unconnected-(IC1-PJ5(PCINT14)-Pad68)") (class "Default")
      (node (ref "IC1") (pin "68") (pinfunction "PJ5(PCINT14)_68") (pintype "bidirectional"))
    )
    (net (code "101") (name "unconnected-(IC1-PJ6(PCINT15)-Pad69)") (class "Default")
      (node (ref "IC1") (pin "69") (pinfunction "PJ6(PCINT15)_69") (pintype "bidirectional"))
    )
    (net (code "102") (name "unconnected-(IC1-PJ7-Pad79)") (class "Default")
      (node (ref "IC1") (pin "79") (pinfunction "PJ7_79") (pintype "bidirectional"))
    )
    (net (code "103") (name "unconnected-(IC1-PK0(ADC8{slash}PCINT16)-Pad89)") (class "Default")
      (node (ref "IC1") (pin "89") (pinfunction "PK0(ADC8/PCINT16)_89") (pintype "bidirectional"))
    )
    (net (code "104") (name "unconnected-(IC1-PK1(ADC9{slash}PCINT17)-Pad88)") (class "Default")
      (node (ref "IC1") (pin "88") (pinfunction "PK1(ADC9/PCINT17)_88") (pintype "bidirectional"))
    )
    (net (code "105") (name "unconnected-(IC1-PK2(ADC10{slash}PCINT18)-Pad87)") (class "Default")
      (node (ref "IC1") (pin "87") (pinfunction "PK2(ADC10/PCINT18)_87") (pintype "bidirectional"))
    )
    (net (code "106") (name "unconnected-(IC1-PK3(ADC11{slash}PCINT19)-Pad86)") (class "Default")
      (node (ref "IC1") (pin "86") (pinfunction "PK3(ADC11/PCINT19)_86") (pintype "bidirectional"))
    )
    (net (code "107") (name "unconnected-(IC1-PL7-Pad42)") (class "Default")
      (node (ref "IC1") (pin "42") (pinfunction "PL7_42") (pintype "bidirectional"))
    )
    (net (code "108") (name "unconnected-(SD_DETECT-Pad2)") (class "Default")
      (node (ref "SD_DETECT") (pin "2") (pinfunction "2_2") (pintype "passive"))
    )
  )
)
